# Mux_2x1.net
KiCad netlist of a schematic drawn in Altium Designer
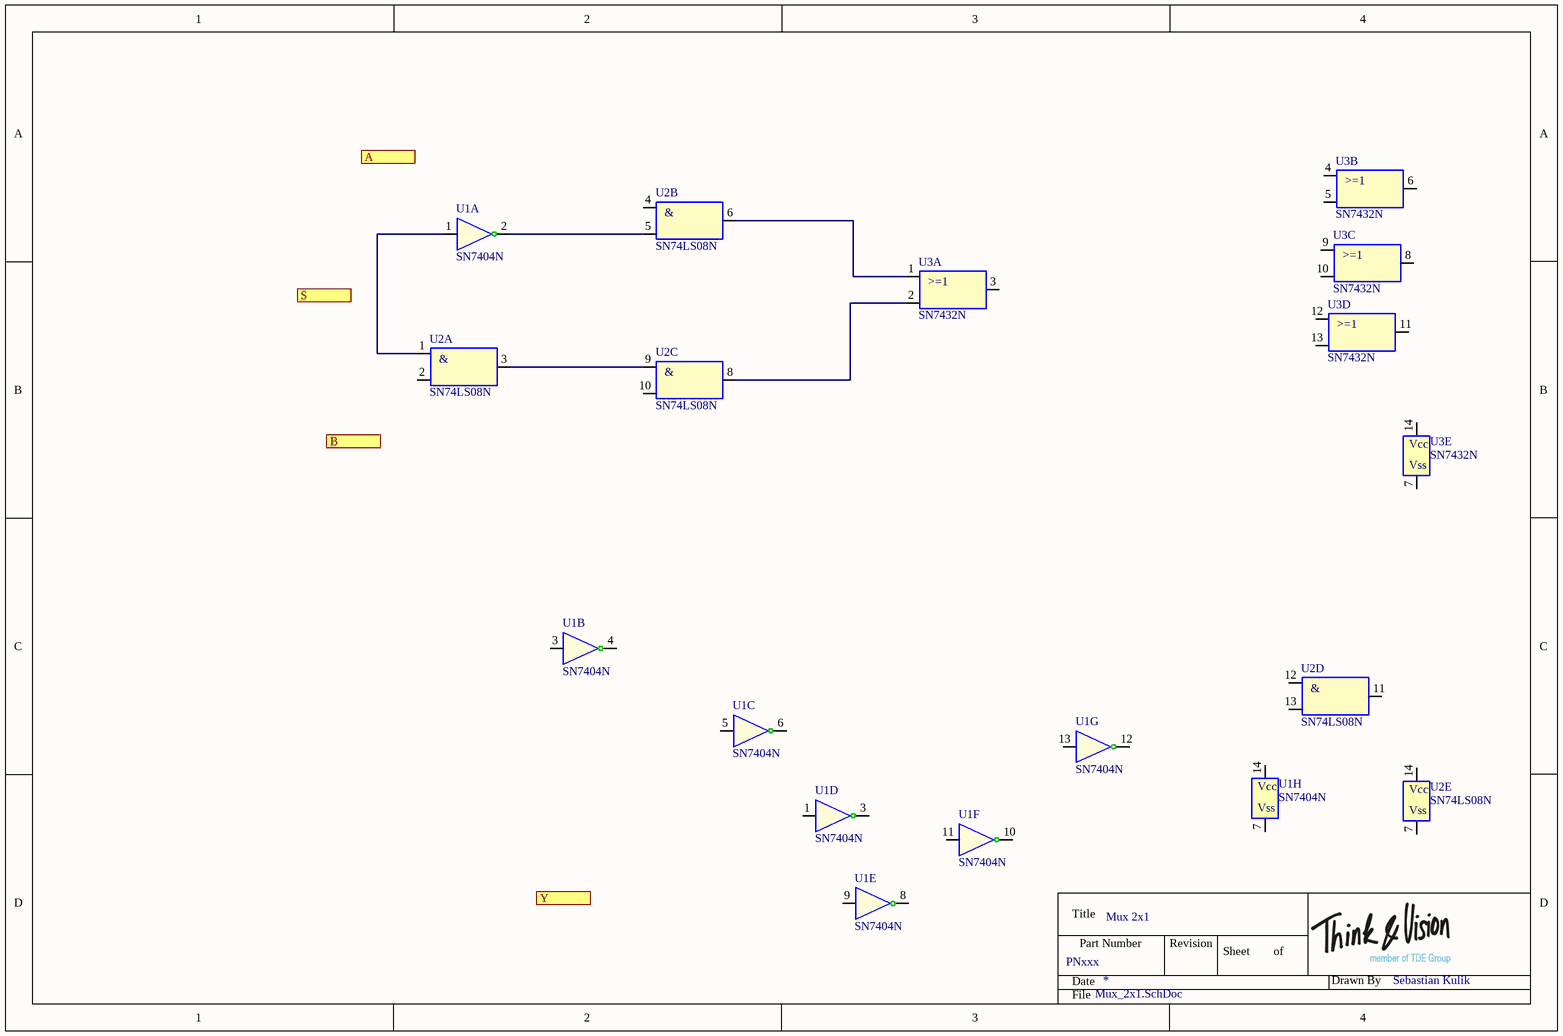
[diagram p0: Mux_2x1.SchDoc]

(export (version "E")
  (design (tool "Eeschema 10.0.6"))
  (components
    (comp (ref "U1")
      (value "SN7404N")
      (footprint "DIP-14")
      (description "Hex Inverter TTL")
      (fields (field (name "MANUFACTURER") "TI") (field (name "PUBLISHER") "Sebastian Kulik"))
      (libsource (lib "ICs") (part "SN7404N"))
    )
    (comp (ref "U2")
      (value "SN74LS08N")
      (footprint "DIP-14")
      (description "Quad AND, TTL")
      (fields (field (name "MANUFACTURER") "TI") (field (name "PUBLISHER") "Sebastian Kulik"))
      (libsource (lib "") (part "SN74LS08N_1"))
    )
    (comp (ref "U3")
      (value "SN7432N")
      (footprint "DIP-14")
      (description "Quad NAND, TTL")
      (fields (field (name "MANUFACTURER") "TI") (field (name "PUBLISHER") "Sebastian Kulik"))
      (libsource (lib "") (part "SN7432N_1"))
    )
  )
  (nets
    (net (code "5") (name "Net-(U1A-1A)") (class "Default")
      (node (ref "U1") (pin "1") (pinfunction "1A_1") (pintype "passive"))
      (node (ref "U2") (pin "1") (pinfunction "1A_1") (pintype "passive"))
    )
    (net (code "6") (name "Net-(U1A-1Y)") (class "Default")
      (node (ref "U1") (pin "2") (pinfunction "1Y_2") (pintype "passive"))
      (node (ref "U2") (pin "5") (pinfunction "2B_5") (pintype "passive"))
    )
    (net (code "7") (name "Net-(U2A-Y1)") (class "Default")
      (node (ref "U2") (pin "3") (pinfunction "Y1_3") (pintype "passive"))
      (node (ref "U2") (pin "9") (pinfunction "3A_9") (pintype "passive"))
    )
    (net (code "8") (name "Net-(U2B-Y2)") (class "Default")
      (node (ref "U2") (pin "6") (pinfunction "Y2_6") (pintype "passive"))
      (node (ref "U3") (pin "1") (pinfunction "1A_1") (pintype "passive"))
    )
    (net (code "9") (name "Net-(U2C-Y3)") (class "Default")
      (node (ref "U2") (pin "8") (pinfunction "Y3_8") (pintype "passive"))
      (node (ref "U3") (pin "2") (pinfunction "1B_2") (pintype "passive"))
    )
    (net (code "10") (name "unconnected-(U1B-2A-Pad3)") (class "Default")
      (node (ref "U1") (pin "3") (pinfunction "2A_3") (pintype "passive"))
    )
    (net (code "11") (name "unconnected-(U1B-2Y-Pad4)") (class "Default")
      (node (ref "U1") (pin "4") (pinfunction "2Y_4") (pintype "passive"))
    )
    (net (code "12") (name "unconnected-(U1C-3A-Pad5)") (class "Default")
      (node (ref "U1") (pin "5") (pinfunction "3A_5") (pintype "passive"))
    )
    (net (code "13") (name "unconnected-(U1C-3Y-Pad6)") (class "Default")
      (node (ref "U1") (pin "6") (pinfunction "3Y_6") (pintype "passive"))
    )
    (net (code "14") (name "unconnected-(U1D-1A-Pad1)") (class "Default")
      (node (ref "U1") (pin "1") (pinfunction "1A_1") (pintype "passive"))
    )
    (net (code "15") (name "unconnected-(U1D-Y1-Pad3)") (class "Default")
      (node (ref "U1") (pin "3") (pinfunction "Y1_3") (pintype "passive"))
    )
    (net (code "16") (name "unconnected-(U1E-4A-Pad9)") (class "Default")
      (node (ref "U1") (pin "9") (pinfunction "4A_9") (pintype "passive"))
    )
    (net (code "17") (name "unconnected-(U1E-4Y-Pad8)") (class "Default")
      (node (ref "U1") (pin "8") (pinfunction "4Y_8") (pintype "passive"))
    )
    (net (code "18") (name "unconnected-(U1F-5A-Pad11)") (class "Default")
      (node (ref "U1") (pin "11") (pinfunction "5A_11") (pintype "passive"))
    )
    (net (code "19") (name "unconnected-(U1F-5Y-Pad10)") (class "Default")
      (node (ref "U1") (pin "10") (pinfunction "5Y_10") (pintype "passive"))
    )
    (net (code "20") (name "unconnected-(U1G-6A-Pad13)") (class "Default")
      (node (ref "U1") (pin "13") (pinfunction "6A_13") (pintype "passive"))
    )
    (net (code "21") (name "unconnected-(U1G-6Y-Pad12)") (class "Default")
      (node (ref "U1") (pin "12") (pinfunction "6Y_12") (pintype "passive"))
    )
    (net (code "22") (name "unconnected-(U1H-Vcc-Pad14)") (class "Default")
      (node (ref "U1") (pin "14") (pinfunction "Vcc_14") (pintype "passive"))
    )
    (net (code "23") (name "unconnected-(U1H-Vss-Pad7)") (class "Default")
      (node (ref "U1") (pin "7") (pinfunction "Vss_7") (pintype "passive"))
    )
    (net (code "24") (name "unconnected-(U2A-1B-Pad2)") (class "Default")
      (node (ref "U2") (pin "2") (pinfunction "1B_2") (pintype "passive"))
    )
    (net (code "25") (name "unconnected-(U2B-2A-Pad4)") (class "Default")
      (node (ref "U2") (pin "4") (pinfunction "2A_4") (pintype "passive"))
    )
    (net (code "26") (name "unconnected-(U2C-3B-Pad10)") (class "Default")
      (node (ref "U2") (pin "10") (pinfunction "3B_10") (pintype "passive"))
    )
    (net (code "27") (name "unconnected-(U2D-4A-Pad12)") (class "Default")
      (node (ref "U2") (pin "12") (pinfunction "4A_12") (pintype "passive"))
    )
    (net (code "28") (name "unconnected-(U2D-4B-Pad13)") (class "Default")
      (node (ref "U2") (pin "13") (pinfunction "4B_13") (pintype "passive"))
    )
    (net (code "29") (name "unconnected-(U2D-Y4-Pad11)") (class "Default")
      (node (ref "U2") (pin "11") (pinfunction "Y4_11") (pintype "passive"))
    )
    (net (code "30") (name "unconnected-(U2E-Vcc-Pad14)") (class "Default")
      (node (ref "U2") (pin "14") (pinfunction "Vcc_14") (pintype "passive"))
    )
    (net (code "31") (name "unconnected-(U2E-Vss-Pad7)") (class "Default")
      (node (ref "U2") (pin "7") (pinfunction "Vss_7") (pintype "passive"))
    )
    (net (code "32") (name "unconnected-(U3A-Y1-Pad3)") (class "Default")
      (node (ref "U3") (pin "3") (pinfunction "Y1_3") (pintype "passive"))
    )
    (net (code "33") (name "unconnected-(U3B-2A-Pad4)") (class "Default")
      (node (ref "U3") (pin "4") (pinfunction "2A_4") (pintype "passive"))
    )
    (net (code "34") (name "unconnected-(U3B-2B-Pad5)") (class "Default")
      (node (ref "U3") (pin "5") (pinfunction "2B_5") (pintype "passive"))
    )
    (net (code "35") (name "unconnected-(U3B-Y2-Pad6)") (class "Default")
      (node (ref "U3") (pin "6") (pinfunction "Y2_6") (pintype "passive"))
    )
    (net (code "36") (name "unconnected-(U3C-3A-Pad9)") (class "Default")
      (node (ref "U3") (pin "9") (pinfunction "3A_9") (pintype "passive"))
    )
    (net (code "37") (name "unconnected-(U3C-3B-Pad10)") (class "Default")
      (node (ref "U3") (pin "10") (pinfunction "3B_10") (pintype "passive"))
    )
    (net (code "38") (name "unconnected-(U3C-Y3-Pad8)") (class "Default")
      (node (ref "U3") (pin "8") (pinfunction "Y3_8") (pintype "passive"))
    )
    (net (code "39") (name "unconnected-(U3D-4A-Pad12)") (class "Default")
      (node (ref "U3") (pin "12") (pinfunction "4A_12") (pintype "passive"))
    )
    (net (code "40") (name "unconnected-(U3D-4B-Pad13)") (class "Default")
      (node (ref "U3") (pin "13") (pinfunction "4B_13") (pintype "passive"))
    )
    (net (code "41") (name "unconnected-(U3D-Y4-Pad11)") (class "Default")
      (node (ref "U3") (pin "11") (pinfunction "Y4_11") (pintype "passive"))
    )
    (net (code "42") (name "unconnected-(U3E-Vcc-Pad14)") (class "Default")
      (node (ref "U3") (pin "14") (pinfunction "Vcc_14") (pintype "passive"))
    )
    (net (code "43") (name "unconnected-(U3E-Vss-Pad7)") (class "Default")
      (node (ref "U3") (pin "7") (pinfunction "Vss_7") (pintype "passive"))
    )
  )
)
